# Sheet1.net
KiCad netlist of a schematic drawn in Altium Designer
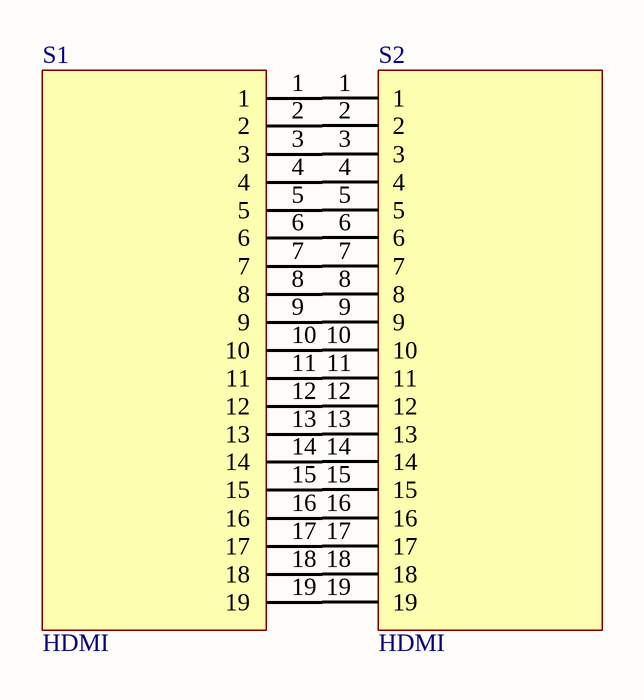
[diagram p0: Sheet1.SchDoc]

(export (version "E")
  (design (tool "Eeschema 10.0.6"))
  (components
    (comp (ref "S1") (value "HDMI") (footprint "HDMI PLUG") (libsource (lib "") (part "HDMI_1")))
    (comp (ref "S2") (value "HDMI") (footprint "HDMI PLUG") (libsource (lib "Schlib1") (part "HDMI")))
  )
  (nets
    (net (code "1") (name "Net-(S1-Pad1)") (class "Default")
      (node (ref "S1") (pin "1") (pinfunction "1_1") (pintype "passive"))
      (node (ref "S2") (pin "1") (pinfunction "1_1") (pintype "passive"))
    )
    (net (code "2") (name "Net-(S1-Pad2)") (class "Default")
      (node (ref "S1") (pin "2") (pinfunction "2_2") (pintype "passive"))
      (node (ref "S2") (pin "2") (pinfunction "2_2") (pintype "passive"))
    )
    (net (code "3") (name "Net-(S1-Pad3)") (class "Default")
      (node (ref "S1") (pin "3") (pinfunction "3_3") (pintype "passive"))
      (node (ref "S2") (pin "3") (pinfunction "3_3") (pintype "passive"))
    )
    (net (code "4") (name "Net-(S1-Pad4)") (class "Default")
      (node (ref "S1") (pin "4") (pinfunction "4_4") (pintype "passive"))
      (node (ref "S2") (pin "4") (pinfunction "4_4") (pintype "passive"))
    )
    (net (code "5") (name "Net-(S1-Pad5)") (class "Default")
      (node (ref "S1") (pin "5") (pinfunction "5_5") (pintype "passive"))
      (node (ref "S2") (pin "5") (pinfunction "5_5") (pintype "passive"))
    )
    (net (code "6") (name "Net-(S1-Pad6)") (class "Default")
      (node (ref "S1") (pin "6") (pinfunction "6_6") (pintype "passive"))
      (node (ref "S2") (pin "6") (pinfunction "6_6") (pintype "passive"))
    )
    (net (code "7") (name "Net-(S1-Pad7)") (class "Default")
      (node (ref "S1") (pin "7") (pinfunction "7_7") (pintype "passive"))
      (node (ref "S2") (pin "7") (pinfunction "7_7") (pintype "passive"))
    )
    (net (code "8") (name "Net-(S1-Pad8)") (class "Default")
      (node (ref "S1") (pin "8") (pinfunction "8_8") (pintype "passive"))
      (node (ref "S2") (pin "8") (pinfunction "8_8") (pintype "passive"))
    )
    (net (code "9") (name "Net-(S1-Pad9)") (class "Default")
      (node (ref "S1") (pin "9") (pinfunction "9_9") (pintype "passive"))
      (node (ref "S2") (pin "9") (pinfunction "9_9") (pintype "passive"))
    )
    (net (code "10") (name "Net-(S1-Pad10)") (class "Default")
      (node (ref "S1") (pin "10") (pinfunction "10_10") (pintype "passive"))
      (node (ref "S2") (pin "10") (pinfunction "10_10") (pintype "passive"))
    )
    (net (code "11") (name "Net-(S1-Pad11)") (class "Default")
      (node (ref "S1") (pin "11") (pinfunction "11_11") (pintype "passive"))
      (node (ref "S2") (pin "11") (pinfunction "11_11") (pintype "passive"))
    )
    (net (code "12") (name "Net-(S1-Pad12)") (class "Default")
      (node (ref "S1") (pin "12") (pinfunction "12_12") (pintype "passive"))
      (node (ref "S2") (pin "12") (pinfunction "12_12") (pintype "passive"))
    )
    (net (code "13") (name "Net-(S1-Pad13)") (class "Default")
      (node (ref "S1") (pin "13") (pinfunction "13_13") (pintype "passive"))
      (node (ref "S2") (pin "13") (pinfunction "13_13") (pintype "passive"))
    )
    (net (code "14") (name "Net-(S1-Pad14)") (class "Default")
      (node (ref "S1") (pin "14") (pinfunction "14_14") (pintype "passive"))
      (node (ref "S2") (pin "14") (pinfunction "14_14") (pintype "passive"))
    )
    (net (code "15") (name "Net-(S1-Pad15)") (class "Default")
      (node (ref "S1") (pin "15") (pinfunction "15_15") (pintype "passive"))
      (node (ref "S2") (pin "15") (pinfunction "15_15") (pintype "passive"))
    )
    (net (code "16") (name "Net-(S1-Pad16)") (class "Default")
      (node (ref "S1") (pin "16") (pinfunction "16_16") (pintype "passive"))
      (node (ref "S2") (pin "16") (pinfunction "16_16") (pintype "passive"))
    )
    (net (code "17") (name "Net-(S1-Pad17)") (class "Default")
      (node (ref "S1") (pin "17") (pinfunction "17_17") (pintype "passive"))
      (node (ref "S2") (pin "17") (pinfunction "17_17") (pintype "passive"))
    )
    (net (code "18") (name "Net-(S1-Pad18)") (class "Default")
      (node (ref "S1") (pin "18") (pinfunction "18_18") (pintype "passive"))
      (node (ref "S2") (pin "18") (pinfunction "18_18") (pintype "passive"))
    )
    (net (code "19") (name "Net-(S1-Pad19)") (class "Default")
      (node (ref "S1") (pin "19") (pinfunction "19_19") (pintype "passive"))
      (node (ref "S2") (pin "19") (pinfunction "19_19") (pintype "passive"))
    )
  )
)
